# Sheet1.net
KiCad netlist of a schematic drawn in Altium Designer
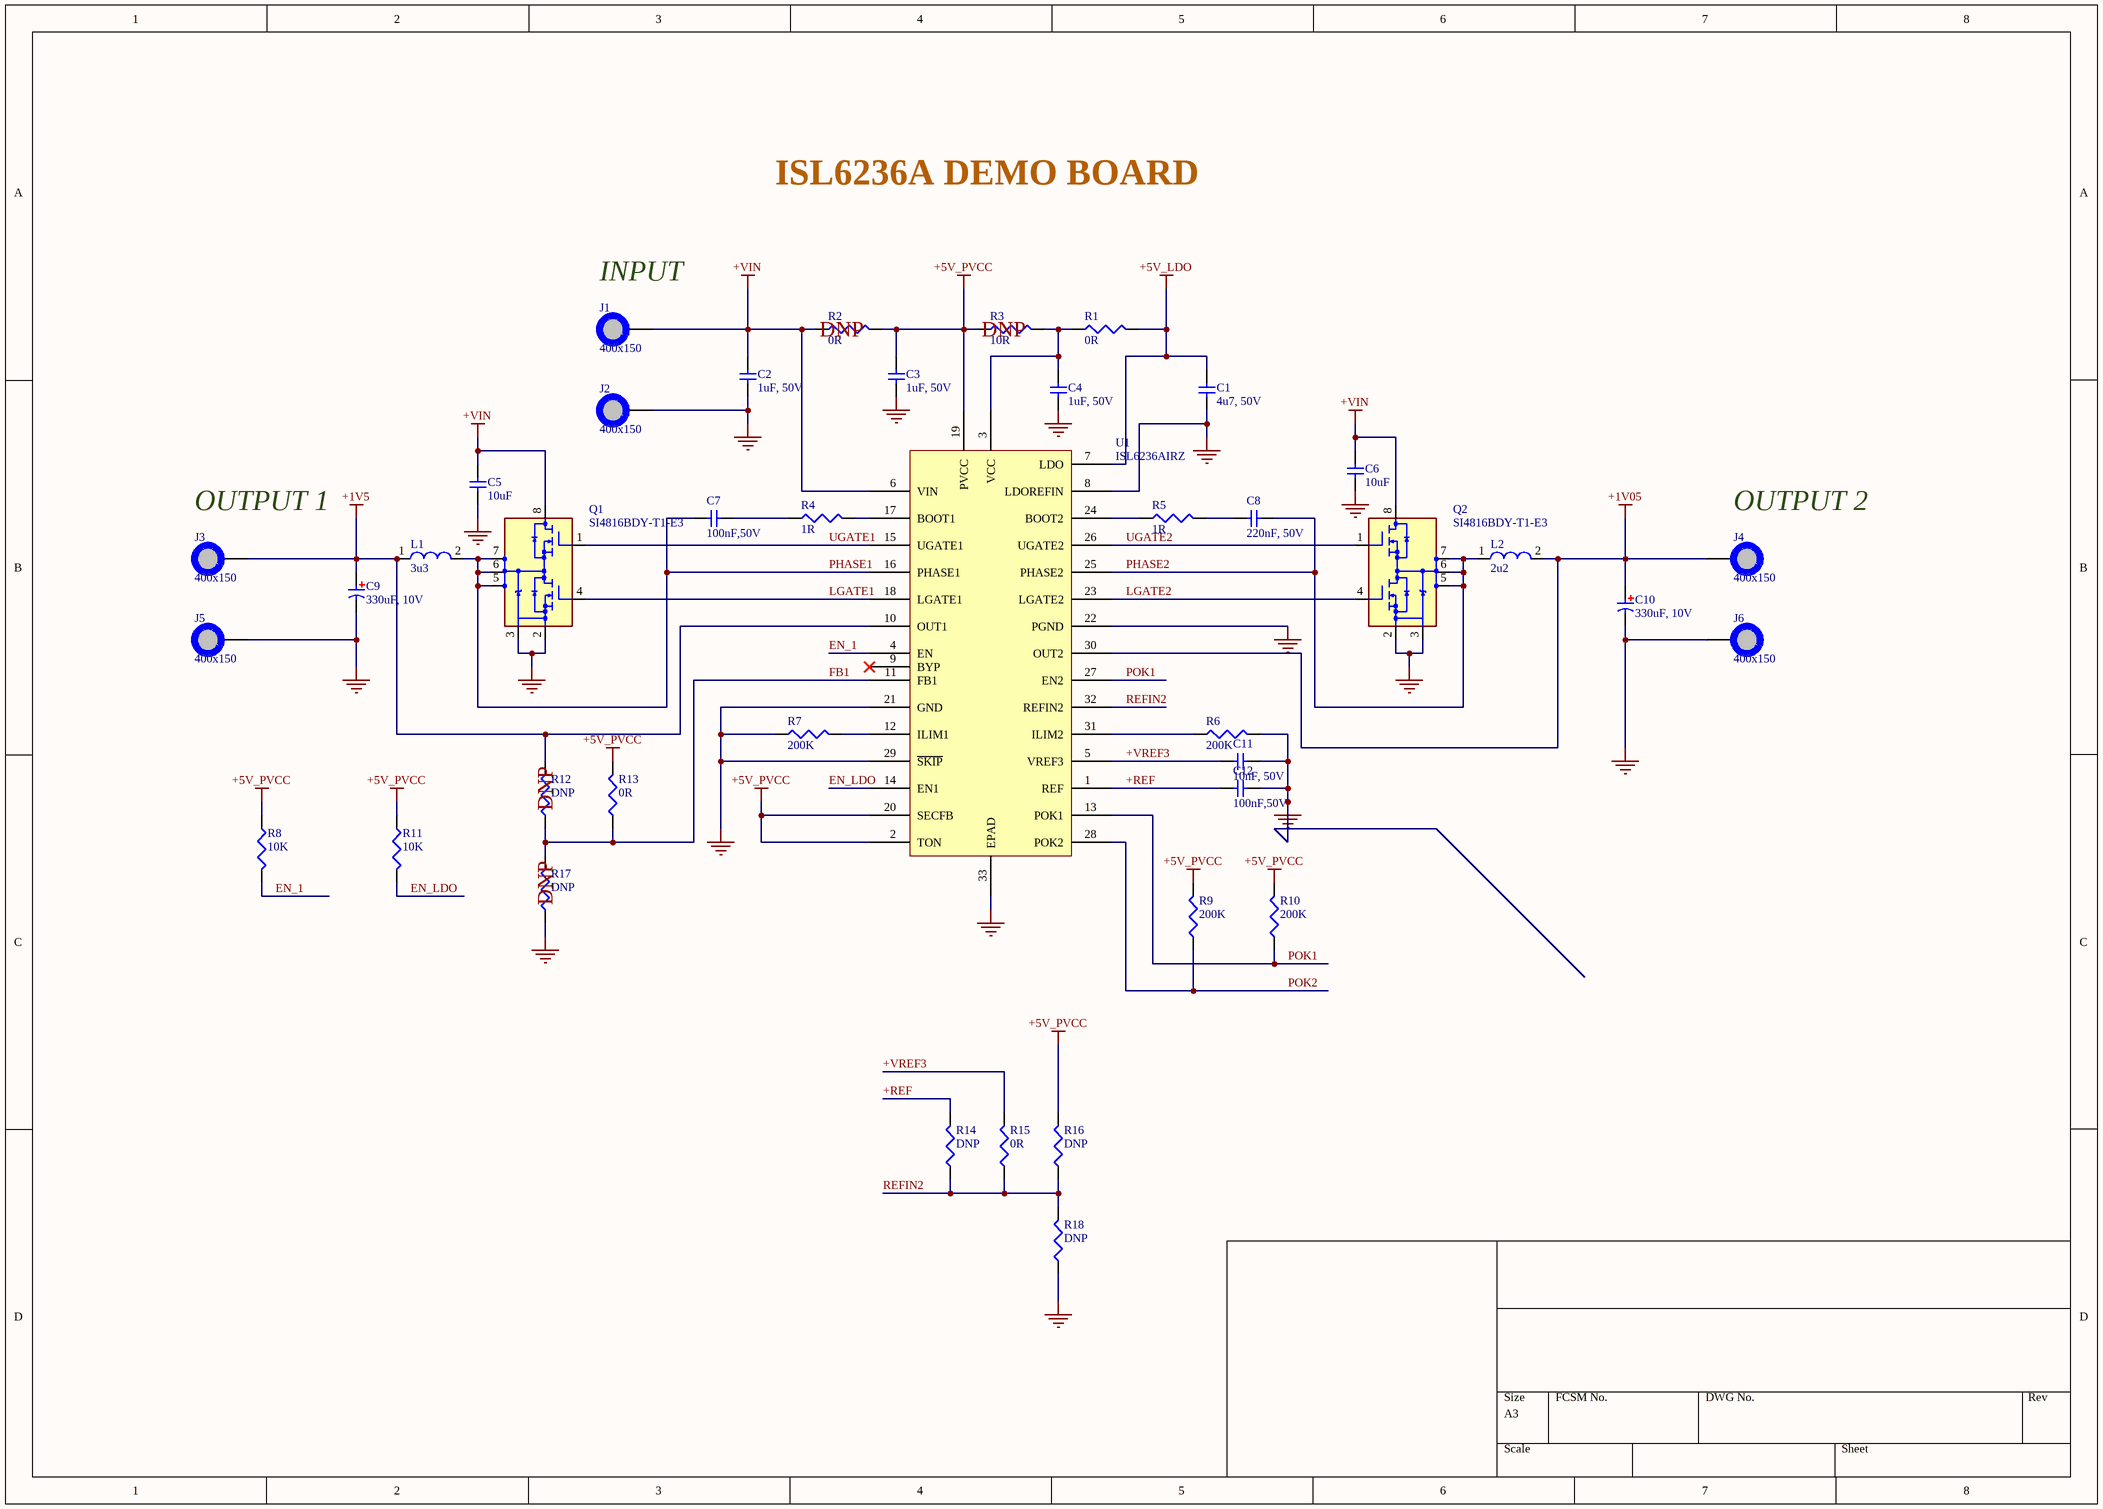
[diagram p0: Sheet1.SchDoc]

(export (version "E")
  (design (tool "Eeschema 10.0.6"))
  (components
    (comp (ref "C1")
      (value "4u7, 50V")
      (footprint "C1206")
      (description "C Series 1206 4.7 uF 50 V ±10 % Tolerance X5R SMT Multilayer Ceramic Capacitor")
      (fields
        (field (name "MANUFACTURER") "TDK")
        (field (name "MANUFACTURER PART NUMBER") "C3216X5R1H475K160AB")
      )
      (libsource (lib "Sheet1_Lib") (part "C3216X5R1H475K160AB"))
    )
    (comp (ref "C2")
      (value "1uF, 50V")
      (footprint "C0805")
      (description "Multilayer Ceramic Capacitor, 1 uF, 50 V, ± 10%, X7R, 0805 [2012 Metric]")
      (fields
        (field (name "MANUFACTURER") "KEMET")
        (field (name "MANUFACTURER PART NUMBER") "C0805C105K5RACTU")
      )
      (libsource (lib "Sheet1_Lib") (part "C0805C105K5RACTU"))
    )
    (comp (ref "C3")
      (value "1uF, 50V")
      (footprint "C0805")
      (description "Multilayer Ceramic Capacitor, 1 uF, 50 V, ± 10%, X7R, 0805 [2012 Metric]")
      (fields
        (field (name "MANUFACTURER") "KEMET")
        (field (name "MANUFACTURER PART NUMBER") "C0805C105K5RACTU")
      )
      (libsource (lib "Sheet1_Lib") (part "C0805C105K5RACTU"))
    )
    (comp (ref "C4")
      (value "1uF, 50V")
      (footprint "C0805")
      (description "Multilayer Ceramic Capacitor, 1 uF, 50 V, ± 10%, X7R, 0805 [2012 Metric]")
      (fields
        (field (name "MANUFACTURER") "KEMET")
        (field (name "MANUFACTURER PART NUMBER") "C0805C105K5RACTU")
      )
      (libsource (lib "Sheet1_Lib") (part "C0805C105K5RACTU"))
    )
    (comp (ref "C5")
      (value "10uF")
      (footprint "C1210")
      (description "Multilayer Ceramic Capacitor, 10 uF, 35 V, ± 10%, X5R, 1210 [3225 Metric]")
      (fields
        (field (name "MANUFACTURER") "KEMET")
        (field (name "MANUFACTURER PART NUMBER") "C1210C106K6PACTU")
      )
      (libsource (lib "Sheet1_Lib") (part "C1210C106K6PACTU"))
    )
    (comp (ref "C6")
      (value "10uF")
      (footprint "C1210")
      (description "Multilayer Ceramic Capacitor, 10 uF, 35 V, ± 10%, X5R, 1210 [3225 Metric]")
      (fields
        (field (name "MANUFACTURER") "KEMET")
        (field (name "MANUFACTURER PART NUMBER") "C1210C106K6PACTU")
      )
      (libsource (lib "Sheet1_Lib") (part "C1210C106K6PACTU"))
    )
    (comp (ref "C7")
      (value "100nF,50V")
      (footprint "C0805")
      (description "Multilayer Ceramic Capacitor, 0.1 uF, 50 V, ± 10%, X7R, 0805 [2012 Metric]")
      (fields
        (field (name "MANUFACTURER") "KEMET")
        (field (name "MANUFACTURER PART NUMBER") "C0805C104K5RACTU")
      )
      (libsource (lib "Sheet1_Lib") (part "C0805C104K5RACTU"))
    )
    (comp (ref "C8")
      (value "220nF, 50V")
      (footprint "C0805")
      (description "Multilayer Ceramic Capacitor, 0.22 uF, 50 V, ± 10%, X7R, 0805 [2012 Metric]")
      (fields
        (field (name "MANUFACTURER") "KEMET")
        (field (name "MANUFACTURER PART NUMBER") "C0805C224K5RACTU")
      )
      (libsource (lib "Sheet1_Lib") (part "C0805C224K5RACTU"))
    )
    (comp (ref "C9")
      (value "330uF, 10V")
      (footprint "7343-43")
      (description "Cap Tant Solid 330uF 10V X CASE 20% (7.3 X 4.3 X 4mm) SMD 7343-43 0.004 Ohm 125 C T/R")
      (fields
        (field (name "MANUFACTURER") "KEMET")
        (field (name "MANUFACTURER PART NUMBER") "T530X337M010ATE004")
      )
      (libsource (lib "Sheet1_Lib") (part "T530X337M010ATE004"))
    )
    (comp (ref "C10")
      (value "330uF, 10V")
      (footprint "7343-43")
      (description "Cap Tant Solid 330uF 10V X CASE 20% (7.3 X 4.3 X 4mm) SMD 7343-43 0.004 Ohm 125 C T/R")
      (fields
        (field (name "MANUFACTURER") "KEMET")
        (field (name "MANUFACTURER PART NUMBER") "T530X337M010ATE004")
      )
      (libsource (lib "Sheet1_Lib") (part "T530X337M010ATE004"))
    )
    (comp (ref "C11")
      (value "10nF, 50V")
      (footprint "C0805")
      (description "0805 C 10nF Ceramic Multilayer Capacitor; 50 VDC; +125degC; X7R Dielec; +/-10%")
      (fields
        (field (name "MANUFACTURER") "KEMET")
        (field (name "MANUFACTURER PART NUMBER") "C0805F103K5RACTU")
      )
      (libsource (lib "Sheet1_Lib") (part "C0805F103K5RACTU"))
    )
    (comp (ref "C12")
      (value "100nF,50V")
      (footprint "C0805")
      (description "Multilayer Ceramic Capacitor, 0.1 uF, 50 V, ± 10%, X7R, 0805 [2012 Metric]")
      (fields
        (field (name "MANUFACTURER") "KEMET")
        (field (name "MANUFACTURER PART NUMBER") "C0805C104K5RACTU")
      )
      (libsource (lib "Sheet1_Lib") (part "C0805C104K5RACTU"))
    )
    (comp (ref "J1")
      (value "400x150")
      (footprint "PAD_400x150")
      (description "Pad with a hole of 4mm x 1.5mm")
      (libsource (lib "Sheet1_Lib") (part "PAD"))
    )
    (comp (ref "J2")
      (value "400x150")
      (footprint "PAD_400x150")
      (description "Pad with a hole of 4mm x 1.5mm")
      (libsource (lib "Sheet1_Lib") (part "PAD"))
    )
    (comp (ref "J3")
      (value "400x150")
      (footprint "PAD_400x150")
      (description "Pad with a hole of 4mm x 1.5mm")
      (libsource (lib "Sheet1_Lib") (part "PAD"))
    )
    (comp (ref "J4")
      (value "400x150")
      (footprint "PAD_400x150")
      (description "Pad with a hole of 4mm x 1.5mm")
      (libsource (lib "Sheet1_Lib") (part "PAD"))
    )
    (comp (ref "J5")
      (value "400x150")
      (footprint "PAD_400x150")
      (description "Pad with a hole of 4mm x 1.5mm")
      (libsource (lib "Sheet1_Lib") (part "PAD"))
    )
    (comp (ref "J6")
      (value "400x150")
      (footprint "PAD_400x150")
      (description "Pad with a hole of 4mm x 1.5mm")
      (libsource (lib "Sheet1_Lib") (part "PAD"))
    )
    (comp (ref "L1")
      (value "3u3")
      (footprint "DR125")
      (description "Inductor Power Shielded Drum Core 3.3uH 20% 100KHz Ferrite 9.26A 6.3mOhm DCR T/R")
      (fields
        (field (name "MANUFACTURER") "Eaton Cooper")
        (field (name "MANUFACTURER PART NUMBER") "DR125-3R3-R")
      )
      (libsource (lib "Sheet1_Lib") (part "DR125-3R3-R"))
    )
    (comp (ref "L2")
      (value "2u2")
      (footprint "DR125")
      (description "Ind Power Shielded Wirewound 2.2uH 20% 100KHz Ferrite 10.9A T/R")
      (fields
        (field (name "MANUFACTURER") "Eaton Cooper")
        (field (name "MANUFACTURER PART NUMBER") "DR125-2R2-R")
      )
      (libsource (lib "Sheet1_Lib") (part "DR125-2R2-R"))
    )
    (comp (ref "Q1")
      (value "SI4816BDY-T1-E3")
      (footprint "SO-8")
      (description "Transistor MOSFET Array Dual N-CH 30V 5.8A/8.2A 8-Pin SOIC T/R")
      (fields (field (name "MANUFACTURER") "Vishay Siliconix"))
      (libsource (lib "Sheet1_Lib") (part "SI4816BDY-T1-E3"))
    )
    (comp (ref "Q2")
      (value "SI4816BDY-T1-E3")
      (footprint "SO-8")
      (description "Transistor MOSFET Array Dual N-CH 30V 5.8A/8.2A 8-Pin SOIC T/R")
      (fields (field (name "MANUFACTURER") "Vishay Siliconix"))
      (libsource (lib "Sheet1_Lib") (part "SI4816BDY-T1-E3"))
    )
    (comp (ref "R1")
      (value "0R")
      (footprint "R0805")
      (description "Zero Ohm Resistor, 0805 [2012 Metric], Thick Film, 125 mW, 2 A, Surface Mount")
      (fields
        (field (name "MANUFACTURER") "Yageo")
        (field (name "MANUFACTURER PART NUMBER") "AC0805JR-070RL")
      )
      (libsource (lib "Sheet1_Lib") (part "AC0805JR-070RL"))
    )
    (comp (ref "R2")
      (value "0R")
      (footprint "R0805")
      (description "Zero Ohm Resistor, 0805 [2012 Metric], Thick Film, 125 mW, 2 A, Surface Mount")
      (fields
        (field (name "MANUFACTURER") "Yageo")
        (field (name "MANUFACTURER PART NUMBER") "AC0805JR-070RL")
      )
      (libsource (lib "Sheet1_Lib") (part "AC0805JR-070RL"))
    )
    (comp (ref "R3")
      (value "10R")
      (footprint "R0805")
      (description "SMD Chip Resistor, 10 Ohm, ± 1%, 125 mW, 0805 [2012 Metric], Thick Film, General Purpose")
      (fields
        (field (name "MANUFACTURER") "Yageo")
        (field (name "MANUFACTURER PART NUMBER") "AC0805FR-0710RL")
      )
      (libsource (lib "Sheet1_Lib") (part "AC0805FR-0710RL"))
    )
    (comp (ref "R4")
      (value "1R")
      (footprint "R0805")
      (description "SMD Chip Resistor, 1 Ohm, ± 1%, 125 mW, 0805 [2012 Metric], Thick Film, General Purpose")
      (fields
        (field (name "MANUFACTURER") "Yageo")
        (field (name "MANUFACTURER PART NUMBER") "AC0805FR-071RL")
      )
      (libsource (lib "Sheet1_Lib") (part "AC0805FR-071RL"))
    )
    (comp (ref "R5")
      (value "1R")
      (footprint "R0805")
      (description "SMD Chip Resistor, 1 Ohm, ± 1%, 125 mW, 0805 [2012 Metric], Thick Film, General Purpose")
      (fields
        (field (name "MANUFACTURER") "Yageo")
        (field (name "MANUFACTURER PART NUMBER") "AC0805FR-071RL")
      )
      (libsource (lib "Sheet1_Lib") (part "AC0805FR-071RL"))
    )
    (comp (ref "R6")
      (value "200K")
      (footprint "R0805")
      (description "SMD Chip Resistor, 200 kOhm, ± 1%, 125 mW, 0805 [2012 Metric], Thick Film, General Purpose")
      (fields
        (field (name "MANUFACTURER") "Yageo")
        (field (name "MANUFACTURER PART NUMBER") "AC0805FR-07200KL")
      )
      (libsource (lib "Sheet1_Lib") (part "AC0805FR-07200KL"))
    )
    (comp (ref "R7")
      (value "200K")
      (footprint "R0805")
      (description "SMD Chip Resistor, 200 kOhm, ± 1%, 125 mW, 0805 [2012 Metric], Thick Film, General Purpose")
      (fields
        (field (name "MANUFACTURER") "Yageo")
        (field (name "MANUFACTURER PART NUMBER") "AC0805FR-07200KL")
      )
      (libsource (lib "Sheet1_Lib") (part "AC0805FR-07200KL"))
    )
    (comp (ref "R8")
      (value "10K")
      (footprint "R0805")
      (description "Res Thick Film 0805 10K Ohm 1% 0.125W(1/8W) ±100ppm/C Pad SMD Automotive T/R")
      (fields
        (field (name "MANUFACTURER") "Yageo")
        (field (name "MANUFACTURER PART NUMBER") "AC0805FR-0710KL")
      )
      (libsource (lib "Sheet1_Lib") (part "AC0805FR-0710KL"))
    )
    (comp (ref "R9")
      (value "200K")
      (footprint "R0805")
      (description "SMD Chip Resistor, 200 kOhm, ± 1%, 125 mW, 0805 [2012 Metric], Thick Film, General Purpose")
      (fields
        (field (name "MANUFACTURER") "Yageo")
        (field (name "MANUFACTURER PART NUMBER") "AC0805FR-07200KL")
      )
      (libsource (lib "Sheet1_Lib") (part "AC0805FR-07200KL"))
    )
    (comp (ref "R10")
      (value "200K")
      (footprint "R0805")
      (description "SMD Chip Resistor, 200 kOhm, ± 1%, 125 mW, 0805 [2012 Metric], Thick Film, General Purpose")
      (fields
        (field (name "MANUFACTURER") "Yageo")
        (field (name "MANUFACTURER PART NUMBER") "AC0805FR-07200KL")
      )
      (libsource (lib "Sheet1_Lib") (part "AC0805FR-07200KL"))
    )
    (comp (ref "R11")
      (value "10K")
      (footprint "R0805")
      (description "Res Thick Film 0805 10K Ohm 1% 0.125W(1/8W) ±100ppm/C Pad SMD Automotive T/R")
      (fields
        (field (name "MANUFACTURER") "Yageo")
        (field (name "MANUFACTURER PART NUMBER") "AC0805FR-0710KL")
      )
      (libsource (lib "Sheet1_Lib") (part "AC0805FR-0710KL"))
    )
    (comp (ref "R12") (value "DNP") (footprint "R0805") (libsource (lib "Sheet1_Lib") (part "RES")))
    (comp (ref "R13")
      (value "0R")
      (footprint "R0805")
      (description "Zero Ohm Resistor, 0805 [2012 Metric], Thick Film, 125 mW, 2 A, Surface Mount")
      (fields
        (field (name "MANUFACTURER") "Yageo")
        (field (name "MANUFACTURER PART NUMBER") "AC0805JR-070RL")
      )
      (libsource (lib "Sheet1_Lib") (part "AC0805JR-070RL"))
    )
    (comp (ref "R14") (value "DNP") (footprint "R0805") (libsource (lib "Sheet1_Lib") (part "RES")))
    (comp (ref "R15")
      (value "0R")
      (footprint "R0805")
      (description "Zero Ohm Resistor, 0805 [2012 Metric], Thick Film, 125 mW, 2 A, Surface Mount")
      (fields
        (field (name "MANUFACTURER") "Yageo")
        (field (name "MANUFACTURER PART NUMBER") "AC0805JR-070RL")
      )
      (libsource (lib "Sheet1_Lib") (part "AC0805JR-070RL"))
    )
    (comp (ref "R16") (value "DNP") (footprint "R0805") (libsource (lib "Sheet1_Lib") (part "RES")))
    (comp (ref "R17") (value "DNP") (footprint "R0805") (libsource (lib "Sheet1_Lib") (part "RES")))
    (comp (ref "R18") (value "DNP") (footprint "R0805") (libsource (lib "Sheet1_Lib") (part "RES")))
    (comp (ref "U1")
      (value "ISL6236AIRZ")
      (footprint "L32.5X5B")
      (description "Soft Sw PWM Cntrlr 2-OUT Power Supply Controller 200KHz/300KHz/400KHz/500KHz 32-Pin QFN EP")
      (fields (field (name "MANUFACTURER") "Renesas"))
      (libsource (lib "Sheet1_Lib") (part "ISL6236AIRZ"))
    )
  )
  (nets
    (net (code "1") (name "+1V05") (class "Default")
      (node (ref "C10") (pin "1") (pinfunction "1_1") (pintype "passive"))
      (node (ref "J4") (pin "1") (pinfunction "1_1") (pintype "passive"))
      (node (ref "L2") (pin "2") (pinfunction "2_2") (pintype "passive"))
      (node (ref "U1") (pin "30") (pinfunction "OUT2_30") (pintype "passive"))
    )
    (net (code "2") (name "+1V5") (class "Default")
      (node (ref "C9") (pin "1") (pinfunction "1_1") (pintype "passive"))
      (node (ref "J3") (pin "1") (pinfunction "1_1") (pintype "passive"))
      (node (ref "L1") (pin "1") (pinfunction "1_1") (pintype "passive"))
      (node (ref "R12") (pin "2") (pinfunction "2_2") (pintype "passive"))
      (node (ref "U1") (pin "10") (pinfunction "OUT1_10") (pintype "passive"))
    )
    (net (code "3") (name "+5V_LDO") (class "Default")
      (node (ref "C1") (pin "2") (pinfunction "2_2") (pintype "passive"))
      (node (ref "R1") (pin "2") (pinfunction "2_2") (pintype "passive"))
      (node (ref "U1") (pin "7") (pinfunction "LDO_7") (pintype "passive"))
    )
    (net (code "4") (name "+5V_PVCC") (class "Default")
      (node (ref "C3") (pin "2") (pinfunction "2_2") (pintype "passive"))
      (node (ref "R10") (pin "2") (pinfunction "2_2") (pintype "passive"))
      (node (ref "R11") (pin "1") (pinfunction "1_1") (pintype "passive"))
      (node (ref "R13") (pin "2") (pinfunction "2_2") (pintype "passive"))
      (node (ref "R16") (pin "2") (pinfunction "2_2") (pintype "passive"))
      (node (ref "R2") (pin "2") (pinfunction "2_2") (pintype "passive"))
      (node (ref "R3") (pin "1") (pinfunction "1_1") (pintype "passive"))
      (node (ref "R8") (pin "1") (pinfunction "1_1") (pintype "passive"))
      (node (ref "R9") (pin "2") (pinfunction "2_2") (pintype "passive"))
      (node (ref "U1") (pin "19") (pinfunction "PVCC_19") (pintype "passive"))
      (node (ref "U1") (pin "2") (pinfunction "TON_2") (pintype "passive"))
      (node (ref "U1") (pin "20") (pinfunction "SECFB_20") (pintype "passive"))
    )
    (net (code "5") (name "+VIN") (class "Default")
      (node (ref "C2") (pin "2") (pinfunction "2_2") (pintype "passive"))
      (node (ref "C5") (pin "2") (pinfunction "2_2") (pintype "passive"))
      (node (ref "C6") (pin "2") (pinfunction "2_2") (pintype "passive"))
      (node (ref "J1") (pin "1") (pinfunction "1_1") (pintype "passive"))
      (node (ref "Q1") (pin "8") (pinfunction "D1_8") (pintype "passive"))
      (node (ref "Q2") (pin "8") (pinfunction "D1_8") (pintype "passive"))
      (node (ref "R2") (pin "1") (pinfunction "1_1") (pintype "passive"))
      (node (ref "U1") (pin "6") (pinfunction "VIN_6") (pintype "passive"))
    )
    (net (code "6") (name "/+REF") (class "Default")
      (node (ref "C12") (pin "1") (pinfunction "1_1") (pintype "passive"))
      (node (ref "R14") (pin "2") (pinfunction "2_2") (pintype "passive"))
      (node (ref "U1") (pin "1") (pinfunction "REF_1") (pintype "passive"))
    )
    (net (code "7") (name "/+VREF3") (class "Default")
      (node (ref "C11") (pin "1") (pinfunction "1_1") (pintype "passive"))
      (node (ref "R15") (pin "2") (pinfunction "2_2") (pintype "passive"))
      (node (ref "U1") (pin "5") (pinfunction "VREF3_5") (pintype "passive"))
    )
    (net (code "8") (name "/EN_1") (class "Default")
      (node (ref "R8") (pin "2") (pinfunction "2_2") (pintype "passive"))
      (node (ref "U1") (pin "4") (pinfunction "EN_4") (pintype "passive"))
    )
    (net (code "9") (name "/EN_LDO") (class "Default")
      (node (ref "R11") (pin "2") (pinfunction "2_2") (pintype "passive"))
      (node (ref "U1") (pin "14") (pinfunction "EN1_14") (pintype "passive"))
    )
    (net (code "10") (name "/FB1") (class "Default")
      (node (ref "R12") (pin "1") (pinfunction "2_1") (pintype "passive"))
      (node (ref "R13") (pin "1") (pinfunction "1_1") (pintype "passive"))
      (node (ref "R17") (pin "2") (pinfunction "2_2") (pintype "passive"))
      (node (ref "U1") (pin "11") (pinfunction "FB1_11") (pintype "passive"))
    )
    (net (code "11") (name "/LGATE1") (class "Default")
      (node (ref "Q1") (pin "4") (pinfunction "G2_4") (pintype "passive"))
      (node (ref "U1") (pin "18") (pinfunction "LGATE1_18") (pintype "passive"))
    )
    (net (code "12") (name "/LGATE2") (class "Default")
      (node (ref "Q2") (pin "4") (pinfunction "G2_4") (pintype "passive"))
      (node (ref "U1") (pin "23") (pinfunction "LGATE2_23") (pintype "passive"))
    )
    (net (code "13") (name "/PHASE1") (class "Default")
      (node (ref "C7") (pin "1") (pinfunction "1_1") (pintype "passive"))
      (node (ref "L1") (pin "2") (pinfunction "2_2") (pintype "passive"))
      (node (ref "Q1") (pin "5") (pinfunction "D2/S1_5") (pintype "passive"))
      (node (ref "Q1") (pin "6") (pinfunction "D2/S1_6") (pintype "passive"))
      (node (ref "Q1") (pin "7") (pinfunction "D2/S1_7") (pintype "passive"))
      (node (ref "U1") (pin "16") (pinfunction "PHASE1_16") (pintype "passive"))
    )
    (net (code "14") (name "/PHASE2") (class "Default")
      (node (ref "C8") (pin "1") (pinfunction "1_1") (pintype "passive"))
      (node (ref "L2") (pin "1") (pinfunction "1_1") (pintype "passive"))
      (node (ref "Q2") (pin "5") (pinfunction "D2/S1_5") (pintype "passive"))
      (node (ref "Q2") (pin "6") (pinfunction "D2/S1_6") (pintype "passive"))
      (node (ref "Q2") (pin "7") (pinfunction "D2/S1_7") (pintype "passive"))
      (node (ref "U1") (pin "25") (pinfunction "PHASE2_25") (pintype "passive"))
    )
    (net (code "15") (name "/POK1") (class "Default")
      (node (ref "R10") (pin "1") (pinfunction "1_1") (pintype "passive"))
      (node (ref "U1") (pin "13") (pinfunction "POK1_13") (pintype "passive"))
      (node (ref "U1") (pin "27") (pinfunction "EN2_27") (pintype "passive"))
    )
    (net (code "16") (name "/POK2") (class "Default")
      (node (ref "R9") (pin "1") (pinfunction "1_1") (pintype "passive"))
      (node (ref "U1") (pin "28") (pinfunction "POK2_28") (pintype "passive"))
    )
    (net (code "17") (name "/REFIN2") (class "Default")
      (node (ref "R14") (pin "1") (pinfunction "2_1") (pintype "passive"))
      (node (ref "R15") (pin "1") (pinfunction "1_1") (pintype "passive"))
      (node (ref "R16") (pin "1") (pinfunction "2_1") (pintype "passive"))
      (node (ref "R18") (pin "2") (pinfunction "2_2") (pintype "passive"))
      (node (ref "U1") (pin "32") (pinfunction "REFIN2_32") (pintype "passive"))
    )
    (net (code "18") (name "/UGATE1") (class "Default")
      (node (ref "Q1") (pin "1") (pinfunction "G1_1") (pintype "passive"))
      (node (ref "U1") (pin "15") (pinfunction "UGATE1_15") (pintype "passive"))
    )
    (net (code "19") (name "/UGATE2") (class "Default")
      (node (ref "Q2") (pin "1") (pinfunction "G1_1") (pintype "passive"))
      (node (ref "U1") (pin "26") (pinfunction "UGATE2_26") (pintype "passive"))
    )
    (net (code "20") (name "GND") (class "Default")
      (node (ref "C1") (pin "1") (pinfunction "1_1") (pintype "passive"))
      (node (ref "C10") (pin "2") (pinfunction "2_2") (pintype "passive"))
      (node (ref "C11") (pin "2") (pinfunction "2_2") (pintype "passive"))
      (node (ref "C12") (pin "2") (pinfunction "2_2") (pintype "passive"))
      (node (ref "C2") (pin "1") (pinfunction "1_1") (pintype "passive"))
      (node (ref "C3") (pin "1") (pinfunction "1_1") (pintype "passive"))
      (node (ref "C4") (pin "1") (pinfunction "1_1") (pintype "passive"))
      (node (ref "C5") (pin "1") (pinfunction "1_1") (pintype "passive"))
      (node (ref "C6") (pin "1") (pinfunction "1_1") (pintype "passive"))
      (node (ref "C9") (pin "2") (pinfunction "2_2") (pintype "passive"))
      (node (ref "J2") (pin "1") (pinfunction "1_1") (pintype "passive"))
      (node (ref "J5") (pin "1") (pinfunction "1_1") (pintype "passive"))
      (node (ref "J6") (pin "1") (pinfunction "1_1") (pintype "passive"))
      (node (ref "Q1") (pin "2") (pinfunction "A/S2_2") (pintype "passive"))
      (node (ref "Q1") (pin "3") (pinfunction "A/S2_3") (pintype "passive"))
      (node (ref "Q2") (pin "2") (pinfunction "A/S2_2") (pintype "passive"))
      (node (ref "Q2") (pin "3") (pinfunction "A/S2_3") (pintype "passive"))
      (node (ref "R17") (pin "1") (pinfunction "2_1") (pintype "passive"))
      (node (ref "R18") (pin "1") (pinfunction "2_1") (pintype "passive"))
      (node (ref "R6") (pin "2") (pinfunction "2_2") (pintype "passive"))
      (node (ref "R7") (pin "1") (pinfunction "1_1") (pintype "passive"))
      (node (ref "U1") (pin "21") (pinfunction "GND_21") (pintype "passive"))
      (node (ref "U1") (pin "22") (pinfunction "PGND_22") (pintype "passive"))
      (node (ref "U1") (pin "29") (pinfunction "~{SKIP}_29") (pintype "passive"))
      (node (ref "U1") (pin "33") (pinfunction "EPAD_33") (pintype "passive"))
      (node (ref "U1") (pin "8") (pinfunction "LDOREFIN_8") (pintype "passive"))
    )
    (net (code "21") (name "Net-(C7-Pad2)") (class "Default")
      (node (ref "C7") (pin "2") (pinfunction "2_2") (pintype "passive"))
      (node (ref "R4") (pin "1") (pinfunction "1_1") (pintype "passive"))
    )
    (net (code "22") (name "Net-(C8-Pad2)") (class "Default")
      (node (ref "C8") (pin "2") (pinfunction "2_2") (pintype "passive"))
      (node (ref "R5") (pin "2") (pinfunction "2_2") (pintype "passive"))
    )
    (net (code "23") (name "Net-(U1-BOOT1)") (class "Default")
      (node (ref "R4") (pin "2") (pinfunction "2_2") (pintype "passive"))
      (node (ref "U1") (pin "17") (pinfunction "BOOT1_17") (pintype "passive"))
    )
    (net (code "24") (name "Net-(U1-BOOT2)") (class "Default")
      (node (ref "R5") (pin "1") (pinfunction "1_1") (pintype "passive"))
      (node (ref "U1") (pin "24") (pinfunction "BOOT2_24") (pintype "passive"))
    )
    (net (code "25") (name "Net-(U1-ILIM1)") (class "Default")
      (node (ref "R7") (pin "2") (pinfunction "2_2") (pintype "passive"))
      (node (ref "U1") (pin "12") (pinfunction "ILIM1_12") (pintype "passive"))
    )
    (net (code "26") (name "Net-(U1-ILIM2)") (class "Default")
      (node (ref "R6") (pin "1") (pinfunction "1_1") (pintype "passive"))
      (node (ref "U1") (pin "31") (pinfunction "ILIM2_31") (pintype "passive"))
    )
    (net (code "27") (name "Net-(U1-VCC)") (class "Default")
      (node (ref "C4") (pin "2") (pinfunction "2_2") (pintype "passive"))
      (node (ref "R1") (pin "1") (pinfunction "1_1") (pintype "passive"))
      (node (ref "R3") (pin "2") (pinfunction "2_2") (pintype "passive"))
      (node (ref "U1") (pin "3") (pinfunction "VCC_3") (pintype "passive"))
    )
    (net (code "28") (name "unconnected-(U1-BYP-Pad9)") (class "Default")
      (node (ref "U1") (pin "9") (pinfunction "BYP_9") (pintype "passive+no_connect"))
    )
  )
)
